# 2.net
KiCad netlist of a schematic drawn in Altium Designer
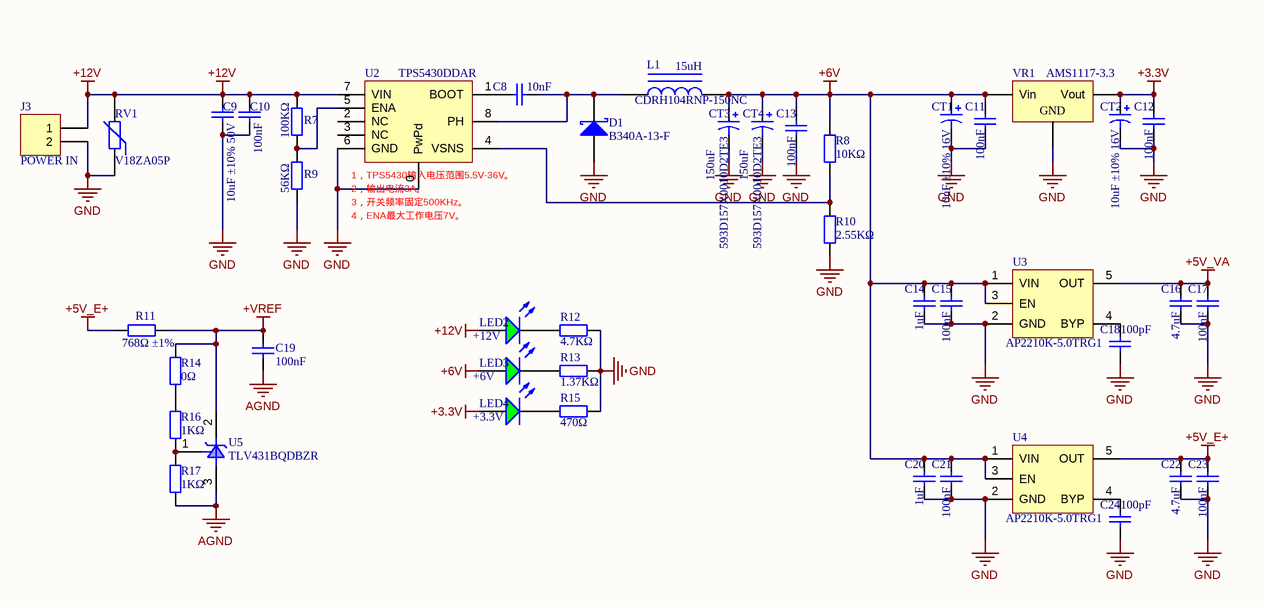
[diagram p0: 2_电子天平_电源.SchDoc]

(export (version "E")
  (design (tool "Eeschema 10.0.6"))
  (components
    (comp (ref "C8")
      (value "10nF")
      (footprint "LC-0805_C")
      (description "MLCC")
      (fields (field (name "PUBLISHER") "Altium Limited"))
      (libsource (lib "Miscellaneous Devices") (part "Cap"))
    )
    (comp (ref "C9")
      (value "10uF ±10% 50V")
      (footprint "LC-1206_C")
      (description "MLCC")
      (fields (field (name "PUBLISHER") "Altium Limited"))
      (libsource (lib "Miscellaneous Devices") (part "Cap"))
    )
    (comp (ref "C10")
      (value "100nF")
      (footprint "LC-0805_C")
      (description "MLCC")
      (fields (field (name "PUBLISHER") "Altium Limited"))
      (libsource (lib "Miscellaneous Devices") (part "Cap"))
    )
    (comp (ref "C11")
      (value "100nF")
      (footprint "LC-0805_C")
      (description "MLCC")
      (fields (field (name "PUBLISHER") "Altium Limited"))
      (libsource (lib "Miscellaneous Devices") (part "Cap"))
    )
    (comp (ref "C12")
      (value "100nF")
      (footprint "LC-0805_C")
      (description "MLCC")
      (fields (field (name "PUBLISHER") "Altium Limited"))
      (libsource (lib "Miscellaneous Devices") (part "Cap"))
    )
    (comp (ref "C13")
      (value "100nF")
      (footprint "LC-1206_C")
      (description "MLCC")
      (fields (field (name "PUBLISHER") "Altium Limited"))
      (libsource (lib "Miscellaneous Devices") (part "Cap"))
    )
    (comp (ref "C14")
      (value "1uF")
      (footprint "LC-0805_C")
      (description "MLCC")
      (fields (field (name "PUBLISHER") "Altium Limited"))
      (libsource (lib "Miscellaneous Devices") (part "Cap"))
    )
    (comp (ref "C15")
      (value "100nF")
      (footprint "LC-0805_C")
      (description "MLCC")
      (fields (field (name "PUBLISHER") "Altium Limited"))
      (libsource (lib "Miscellaneous Devices") (part "Cap"))
    )
    (comp (ref "C16")
      (value "4.7uF")
      (footprint "LC-0805_C")
      (description "MLCC")
      (fields (field (name "PUBLISHER") "Altium Limited"))
      (libsource (lib "Miscellaneous Devices") (part "Cap"))
    )
    (comp (ref "C17")
      (value "100nF")
      (footprint "LC-0805_C")
      (description "MLCC")
      (fields (field (name "PUBLISHER") "Altium Limited"))
      (libsource (lib "Miscellaneous Devices") (part "Cap"))
    )
    (comp (ref "C18")
      (value "100pF")
      (footprint "LC-0805_C")
      (description "MLCC")
      (fields (field (name "PUBLISHER") "Altium Limited"))
      (libsource (lib "Miscellaneous Devices") (part "Cap"))
    )
    (comp (ref "C19")
      (value "100nF")
      (footprint "LC-0805_C")
      (description "MLCC")
      (fields (field (name "PUBLISHER") "Altium Limited"))
      (libsource (lib "Miscellaneous Devices") (part "Cap"))
    )
    (comp (ref "C20")
      (value "1uF")
      (footprint "LC-0805_C")
      (description "MLCC")
      (fields (field (name "PUBLISHER") "Altium Limited"))
      (libsource (lib "Miscellaneous Devices") (part "Cap"))
    )
    (comp (ref "C21")
      (value "100nF")
      (footprint "LC-0805_C")
      (description "MLCC")
      (fields (field (name "PUBLISHER") "Altium Limited"))
      (libsource (lib "Miscellaneous Devices") (part "Cap"))
    )
    (comp (ref "C22")
      (value "4.7uF")
      (footprint "LC-0805_C")
      (description "MLCC")
      (fields (field (name "PUBLISHER") "Altium Limited"))
      (libsource (lib "Miscellaneous Devices") (part "Cap"))
    )
    (comp (ref "C23")
      (value "100nF")
      (footprint "LC-0805_C")
      (description "MLCC")
      (fields (field (name "PUBLISHER") "Altium Limited"))
      (libsource (lib "Miscellaneous Devices") (part "Cap"))
    )
    (comp (ref "C24")
      (value "100pF")
      (footprint "LC-0805_C")
      (description "MLCC")
      (fields (field (name "PUBLISHER") "Altium Limited"))
      (libsource (lib "Miscellaneous Devices") (part "Cap"))
    )
    (comp (ref "CT1")
      (value "10uF ±10% 16V")
      (footprint "LC-CASE-A_3216")
      (description "钽电容")
      (fields (field (name "PUBLISHER") "Altium Limited"))
      (libsource (lib "Miscellaneous Devices") (part "Cap Pol1"))
    )
    (comp (ref "CT2")
      (value "10uF ±10% 16V")
      (footprint "LC-CASE-A_3216")
      (description "钽电容")
      (fields (field (name "PUBLISHER") "Altium Limited"))
      (libsource (lib "Miscellaneous Devices") (part "Cap Pol1"))
    )
    (comp (ref "CT3")
      (value "593D157X0010D2TE3")
      (footprint "LC-CASE-D_7343")
      (description "钽电容")
      (fields (field (name "ALTIUM_VALUE") "150uF") (field (name "PUBLISHER") "Altium Limited"))
      (libsource (lib "Miscellaneous Devices") (part "Cap Pol1"))
    )
    (comp (ref "CT4")
      (value "593D157X0010D2TE3")
      (footprint "LC-CASE-D_7343")
      (description "钽电容")
      (fields (field (name "ALTIUM_VALUE") "150uF") (field (name "PUBLISHER") "Altium Limited"))
      (libsource (lib "Miscellaneous Devices") (part "Cap Pol1"))
    )
    (comp (ref "D1")
      (value "B340A-13-F")
      (footprint "LC-SMA(DO-214AC)_S1")
      (description "肖特基二极管")
      (fields (field (name "PUBLISHER") "Altium Limited"))
      (libsource (lib "Miscellaneous Devices") (part "D Schottky"))
    )
    (comp (ref "J3")
      (value "POWER IN")
      (footprint "CON-VH7.92-2P")
      (description "Header, 2-Pin")
      (fields (field (name "PUBLISHER") "Altium Limited"))
      (libsource (lib "Miscellaneous Connectors") (part "Header 2"))
    )
    (comp (ref "L1")
      (value "CDRH104RNP-150NC")
      (footprint "L-CDRH104R")
      (description "Magnetic-Core Inductor")
      (fields (field (name "ALTIUM_VALUE") "15uH") (field (name "PUBLISHER") "Altium Limited"))
      (libsource (lib "Miscellaneous Devices") (part "Inductor Iron"))
    )
    (comp (ref "LED2")
      (value "+12V")
      (footprint "LC-0805_LED_S1")
      (description "发光二极管")
      (libsource (lib "Miscellaneous Devices LC") (part "0805 翠绿"))
    )
    (comp (ref "LED3")
      (value "+6V")
      (footprint "LC-0805_LED_S1")
      (description "发光二极管")
      (libsource (lib "Miscellaneous Devices LC") (part "0805 翠绿"))
    )
    (comp (ref "LED4")
      (value "+3.3V")
      (footprint "LC-0805_LED_S1")
      (description "发光二极管")
      (libsource (lib "Miscellaneous Devices LC") (part "0805 翠绿"))
    )
    (comp (ref "R7")
      (value "100KΩ")
      (footprint "LC-0805_R")
      (description "Resistor")
      (fields (field (name "PUBLISHER") "Altium Limited"))
      (libsource (lib "") (part "Res2_1"))
    )
    (comp (ref "R8")
      (value "10KΩ")
      (footprint "LC-0805_R")
      (description "Resistor")
      (fields (field (name "PUBLISHER") "Altium Limited"))
      (libsource (lib "Miscellaneous Devices") (part "Res2"))
    )
    (comp (ref "R9")
      (value "56KΩ")
      (footprint "LC-0805_R")
      (description "Resistor")
      (fields (field (name "PUBLISHER") "Altium Limited"))
      (libsource (lib "") (part "Res2_1"))
    )
    (comp (ref "R10")
      (value "2.55KΩ")
      (footprint "LC-0805_R")
      (description "Resistor")
      (fields (field (name "PUBLISHER") "Altium Limited"))
      (libsource (lib "Miscellaneous Devices") (part "Res2"))
    )
    (comp (ref "R11")
      (value "768Ω ±1%")
      (footprint "LC-0805_R")
      (description "Resistor")
      (fields (field (name "PUBLISHER") "Altium Limited"))
      (libsource (lib "") (part "Res2_2"))
    )
    (comp (ref "R12")
      (value "4.7KΩ")
      (footprint "LC-0805_R")
      (description "贴片电阻")
      (libsource (lib "Miscellaneous Devices LC") (part "0805 47KΩ (4702) 1%"))
    )
    (comp (ref "R13")
      (value "1.37KΩ")
      (footprint "LC-0805_R")
      (description "贴片电阻")
      (libsource (lib "Miscellaneous Devices LC") (part "0805 47KΩ (4702) 1%"))
    )
    (comp (ref "R14")
      (value "0Ω")
      (footprint "LC-0805_R")
      (description "贴片电阻")
      (libsource (lib "Miscellaneous Devices LC") (part "0805 470KΩ (4703) 1%"))
    )
    (comp (ref "R15")
      (value "470Ω")
      (footprint "LC-0805_R")
      (description "贴片电阻")
      (libsource (lib "Miscellaneous Devices LC") (part "0805 47KΩ (4702) 1%"))
    )
    (comp (ref "R16")
      (value "1KΩ")
      (footprint "LC-0805_R")
      (description "贴片电阻")
      (libsource (lib "Miscellaneous Devices LC") (part "0805 470KΩ (4703) 1%"))
    )
    (comp (ref "R17")
      (value "1KΩ")
      (footprint "LC-0805_R")
      (description "贴片电阻")
      (libsource (lib "") (part "0805 470KΩ (4703) 1%_1"))
    )
    (comp (ref "RV1")
      (value "V18ZA05P")
      (footprint "RV-V18ZA05P")
      (description "Varistor (Voltage-Sensitive Resistor)")
      (fields (field (name "PUBLISHER") "Altium Limited"))
      (libsource (lib "Miscellaneous Devices") (part "Res Varistor"))
    )
    (comp (ref "U2")
      (value "TPS5430DDAR")
      (footprint "LC-SOP-8_EP_150mil")
      (description "5.5V to 36V Input, 3A, Step-Down DC-DC")
      (libsource (lib "Riggin") (part "TPS5430DDAR"))
    )
    (comp (ref "U3")
      (value "AP2210K-5.0TRG1")
      (footprint "LC-SOT-23-5")
      (description "5.0V固定输出，低压差700mV@Iout=500mA，Vin=16V")
      (libsource (lib "Riggin") (part "SPX3819M5-L-5-0/TR"))
    )
    (comp (ref "U4")
      (value "AP2210K-5.0TRG1")
      (footprint "LC-SOT-23-5")
      (description "5.0V固定输出，低压差700mV@Iout=500mA，Vin=16V")
      (libsource (lib "Riggin") (part "SPX3819M5-L-5-0/TR"))
    )
    (comp (ref "U5")
      (value "TLV431BQDBZR")
      (footprint "LC-SOT-23(SOT-23-3)")
      (description "电压基准")
      (libsource (lib "Miscellaneous Devices LC") (part "CJ431 0.5%431"))
    )
    (comp (ref "VR1")
      (value "AMS1117-3.3")
      (footprint "LC-SOT-223")
      (description "低压差线性稳压(LDO)")
      (libsource (lib "Miscellaneous Devices LC") (part "SOT-223 AMS1117-3.3"))
    )
  )
  (nets
    (net (code "1") (name "+3.3V") (class "Default")
      (node (ref "C12") (pin "1") (pinfunction "1_1") (pintype "passive"))
      (node (ref "CT2") (pin "1") (pinfunction "1_1") (pintype "passive"))
      (node (ref "LED4") (pin "A") (pinfunction "A_A") (pintype "passive"))
      (node (ref "VR1") (pin "2") (pinfunction "Vout_2") (pintype "passive"))
    )
    (net (code "2") (name "+5V_E+") (class "Default")
      (node (ref "C22") (pin "1") (pinfunction "1_1") (pintype "passive"))
      (node (ref "C23") (pin "1") (pinfunction "1_1") (pintype "passive"))
      (node (ref "R11") (pin "1") (pinfunction "1_1") (pintype "passive"))
      (node (ref "U4") (pin "5") (pinfunction "OUT_5") (pintype "passive"))
    )
    (net (code "3") (name "+5V_VA") (class "Default")
      (node (ref "C16") (pin "1") (pinfunction "1_1") (pintype "passive"))
      (node (ref "C17") (pin "1") (pinfunction "1_1") (pintype "passive"))
      (node (ref "U3") (pin "5") (pinfunction "OUT_5") (pintype "passive"))
    )
    (net (code "4") (name "+6V") (class "Default")
      (node (ref "C11") (pin "1") (pinfunction "1_1") (pintype "passive"))
      (node (ref "C13") (pin "1") (pinfunction "1_1") (pintype "passive"))
      (node (ref "C14") (pin "1") (pinfunction "1_1") (pintype "passive"))
      (node (ref "C15") (pin "1") (pinfunction "1_1") (pintype "passive"))
      (node (ref "C20") (pin "1") (pinfunction "1_1") (pintype "passive"))
      (node (ref "C21") (pin "1") (pinfunction "1_1") (pintype "passive"))
      (node (ref "CT1") (pin "1") (pinfunction "1_1") (pintype "passive"))
      (node (ref "CT3") (pin "1") (pinfunction "1_1") (pintype "passive"))
      (node (ref "CT4") (pin "1") (pinfunction "1_1") (pintype "passive"))
      (node (ref "L1") (pin "2") (pinfunction "2_2") (pintype "passive"))
      (node (ref "LED3") (pin "A") (pinfunction "A_A") (pintype "passive"))
      (node (ref "R8") (pin "1") (pinfunction "1_1") (pintype "passive"))
      (node (ref "U3") (pin "1") (pinfunction "VIN_1") (pintype "passive"))
      (node (ref "U3") (pin "3") (pinfunction "EN_3") (pintype "passive"))
      (node (ref "U4") (pin "1") (pinfunction "VIN_1") (pintype "passive"))
      (node (ref "U4") (pin "3") (pinfunction "EN_3") (pintype "passive"))
      (node (ref "VR1") (pin "3") (pinfunction "Vin_3") (pintype "passive"))
    )
    (net (code "5") (name "+12V") (class "Default")
      (node (ref "C10") (pin "1") (pinfunction "1_1") (pintype "passive"))
      (node (ref "C9") (pin "1") (pinfunction "1_1") (pintype "passive"))
      (node (ref "J3") (pin "1") (pinfunction "1_1") (pintype "passive"))
      (node (ref "LED2") (pin "A") (pinfunction "A_A") (pintype "passive"))
      (node (ref "R7") (pin "2") (pinfunction "2_2") (pintype "passive"))
      (node (ref "RV1") (pin "2") (pinfunction "2_2") (pintype "passive"))
      (node (ref "U2") (pin "7") (pinfunction "VIN_7") (pintype "passive"))
    )
    (net (code "6") (name "+VREF") (class "Default")
      (node (ref "C19") (pin "2") (pinfunction "2_2") (pintype "passive"))
      (node (ref "R11") (pin "2") (pinfunction "2_2") (pintype "passive"))
      (node (ref "R14") (pin "2") (pinfunction "2_2") (pintype "passive"))
      (node (ref "U5") (pin "2") (pinfunction "K_2") (pintype "passive"))
    )
    (net (code "7") (name "AGND") (class "Default")
      (node (ref "C19") (pin "1") (pinfunction "1_1") (pintype "passive"))
      (node (ref "R17") (pin "2") (pinfunction "2_2") (pintype "passive"))
      (node (ref "U5") (pin "3") (pinfunction "A_3") (pintype "passive"))
    )
    (net (code "8") (name "GND") (class "Default")
      (node (ref "C10") (pin "2") (pinfunction "2_2") (pintype "passive"))
      (node (ref "C11") (pin "2") (pinfunction "2_2") (pintype "passive"))
      (node (ref "C12") (pin "2") (pinfunction "2_2") (pintype "passive"))
      (node (ref "C13") (pin "2") (pinfunction "2_2") (pintype "passive"))
      (node (ref "C14") (pin "2") (pinfunction "2_2") (pintype "passive"))
      (node (ref "C15") (pin "2") (pinfunction "2_2") (pintype "passive"))
      (node (ref "C16") (pin "2") (pinfunction "2_2") (pintype "passive"))
      (node (ref "C17") (pin "2") (pinfunction "2_2") (pintype "passive"))
      (node (ref "C18") (pin "2") (pinfunction "2_2") (pintype "passive"))
      (node (ref "C20") (pin "2") (pinfunction "2_2") (pintype "passive"))
      (node (ref "C21") (pin "2") (pinfunction "2_2") (pintype "passive"))
      (node (ref "C22") (pin "2") (pinfunction "2_2") (pintype "passive"))
      (node (ref "C23") (pin "2") (pinfunction "2_2") (pintype "passive"))
      (node (ref "C24") (pin "2") (pinfunction "2_2") (pintype "passive"))
      (node (ref "C9") (pin "2") (pinfunction "2_2") (pintype "passive"))
      (node (ref "CT1") (pin "2") (pinfunction "2_2") (pintype "passive"))
      (node (ref "CT2") (pin "2") (pinfunction "2_2") (pintype "passive"))
      (node (ref "CT3") (pin "2") (pinfunction "2_2") (pintype "passive"))
      (node (ref "CT4") (pin "2") (pinfunction "2_2") (pintype "passive"))
      (node (ref "D1") (pin "1") (pinfunction "A_1") (pintype "passive"))
      (node (ref "J3") (pin "2") (pinfunction "2_2") (pintype "passive"))
      (node (ref "R10") (pin "2") (pinfunction "2_2") (pintype "passive"))
      (node (ref "R12") (pin "1") (pinfunction "1_1") (pintype "passive"))
      (node (ref "R13") (pin "1") (pinfunction "1_1") (pintype "passive"))
      (node (ref "R15") (pin "1") (pinfunction "1_1") (pintype "passive"))
      (node (ref "R9") (pin "1") (pinfunction "1_1") (pintype "passive"))
      (node (ref "RV1") (pin "1") (pinfunction "1_1") (pintype "passive"))
      (node (ref "U2") (pin "0") (pinfunction "PwPd_0") (pintype "passive"))
      (node (ref "U2") (pin "6") (pinfunction "GND_6") (pintype "passive"))
      (node (ref "U3") (pin "2") (pinfunction "GND_2") (pintype "passive"))
      (node (ref "U4") (pin "2") (pinfunction "GND_2") (pintype "passive"))
      (node (ref "VR1") (pin "1") (pinfunction "GND_1") (pintype "passive"))
    )
    (net (code "9") (name "Net-(D1-K)") (class "Default")
      (node (ref "C8") (pin "2") (pinfunction "2_2") (pintype "passive"))
      (node (ref "D1") (pin "2") (pinfunction "K_2") (pintype "passive"))
      (node (ref "L1") (pin "1") (pinfunction "1_1") (pintype "passive"))
      (node (ref "U2") (pin "8") (pinfunction "PH_8") (pintype "passive"))
    )
    (net (code "10") (name "Net-(LED2-PadK)") (class "Default")
      (node (ref "LED2") (pin "K") (pinfunction "K_K") (pintype "passive"))
      (node (ref "R12") (pin "2") (pinfunction "2_2") (pintype "passive"))
    )
    (net (code "11") (name "Net-(LED3-PadK)") (class "Default")
      (node (ref "LED3") (pin "K") (pinfunction "K_K") (pintype "passive"))
      (node (ref "R13") (pin "2") (pinfunction "2_2") (pintype "passive"))
    )
    (net (code "12") (name "Net-(LED4-PadK)") (class "Default")
      (node (ref "LED4") (pin "K") (pinfunction "K_K") (pintype "passive"))
      (node (ref "R15") (pin "2") (pinfunction "2_2") (pintype "passive"))
    )
    (net (code "13") (name "Net-(R14-Pad1)") (class "Default")
      (node (ref "R14") (pin "1") (pinfunction "1_1") (pintype "passive"))
      (node (ref "R16") (pin "2") (pinfunction "2_2") (pintype "passive"))
    )
    (net (code "14") (name "Net-(U2-BOOT)") (class "Default")
      (node (ref "C8") (pin "1") (pinfunction "1_1") (pintype "passive"))
      (node (ref "U2") (pin "1") (pinfunction "BOOT_1") (pintype "passive"))
    )
    (net (code "15") (name "Net-(U2-ENA)") (class "Default")
      (node (ref "R7") (pin "1") (pinfunction "1_1") (pintype "passive"))
      (node (ref "R9") (pin "2") (pinfunction "2_2") (pintype "passive"))
      (node (ref "U2") (pin "5") (pinfunction "ENA_5") (pintype "passive"))
    )
    (net (code "16") (name "Net-(U2-VSNS)") (class "Default")
      (node (ref "R10") (pin "1") (pinfunction "1_1") (pintype "passive"))
      (node (ref "R8") (pin "2") (pinfunction "2_2") (pintype "passive"))
      (node (ref "U2") (pin "4") (pinfunction "VSNS_4") (pintype "passive"))
    )
    (net (code "17") (name "Net-(U3-BYP)") (class "Default")
      (node (ref "C18") (pin "1") (pinfunction "1_1") (pintype "passive"))
      (node (ref "U3") (pin "4") (pinfunction "BYP_4") (pintype "passive"))
    )
    (net (code "18") (name "Net-(U4-BYP)") (class "Default")
      (node (ref "C24") (pin "1") (pinfunction "1_1") (pintype "passive"))
      (node (ref "U4") (pin "4") (pinfunction "BYP_4") (pintype "passive"))
    )
    (net (code "19") (name "Net-(U5-R)") (class "Default")
      (node (ref "R16") (pin "1") (pinfunction "1_1") (pintype "passive"))
      (node (ref "R17") (pin "1") (pinfunction "1_1") (pintype "passive"))
      (node (ref "U5") (pin "1") (pinfunction "R_1") (pintype "passive"))
    )
    (net (code "20") (name "unconnected-(U2-NC-Pad2)") (class "Default")
      (node (ref "U2") (pin "2") (pinfunction "NC_2") (pintype "passive"))
    )
    (net (code "21") (name "unconnected-(U2-NC-Pad3)") (class "Default")
      (node (ref "U2") (pin "3") (pinfunction "NC_3") (pintype "passive"))
    )
  )
)
